# LEDProbe.net
KiCad netlist of a schematic drawn in EAGLE
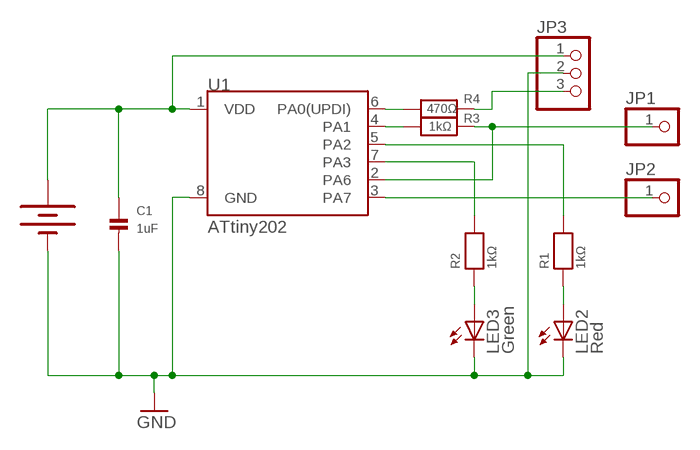
[diagram p0: schematic, sheet 1]

(export (version "E")
  (design (tool "Eeschema 10.0.6"))
  (components
    (comp (ref "BAT2")
      (value "20mm coincell")
      (footprint "eagle-import:BATTCON_20MM_4LEGS")
      (libsource (lib "eagle-import") (part "BATTERY20MM_4LEGS"))
    )
    (comp (ref "C1")
      (value "1uF")
      (footprint "eagle-import:_0805MP")
      (libsource (lib "eagle-import") (part "CAP_CERAMIC_0805MP"))
    )
    (comp (ref "JP1")
      (value "PINHD-1X1CB")
      (footprint "eagle-import:1X01-CLEANBIG")
      (libsource (lib "eagle-import") (part "PINHD-1X1CB"))
    )
    (comp (ref "JP2")
      (value "PINHD-1X1CB")
      (footprint "eagle-import:1X01-CLEANBIG")
      (libsource (lib "eagle-import") (part "PINHD-1X1CB"))
    )
    (comp (ref "JP3")
      (value "PINHD-1X3CB")
      (footprint "eagle-import:1X03-CLEANBIG")
      (libsource (lib "eagle-import") (part "PINHD-1X3CB"))
    )
    (comp (ref "LED2")
      (value "Red")
      (footprint "eagle-import:CHIPLED_0805")
      (libsource (lib "eagle-import") (part "LEDCHIPLED_0805"))
    )
    (comp (ref "LED3")
      (value "Green")
      (footprint "eagle-import:CHIPLED_0805")
      (libsource (lib "eagle-import") (part "LEDCHIPLED_0805"))
    )
    (comp (ref "R1")
      (value "1kΩ")
      (footprint "eagle-import:_0805MP")
      (libsource (lib "eagle-import") (part "RESISTOR_0805MP"))
    )
    (comp (ref "R2")
      (value "1kΩ")
      (footprint "eagle-import:_0805MP")
      (libsource (lib "eagle-import") (part "RESISTOR_0805MP"))
    )
    (comp (ref "R3")
      (value "1kΩ")
      (footprint "eagle-import:_0805MP")
      (libsource (lib "eagle-import") (part "RESISTOR_0805MP"))
    )
    (comp (ref "R4")
      (value "470Ω")
      (footprint "eagle-import:_0805MP")
      (libsource (lib "eagle-import") (part "RESISTOR_0805MP"))
    )
    (comp (ref "U1")
      (value "ATtiny202")
      (footprint "eagle-import:SO08-EIAJ")
      (libsource (lib "eagle-import") (part "ATTINY402ATTINY402-SMT"))
    )
  )
  (nets
    (net (code "1") (name "GND") (class "Default")
      (node (ref "BAT2") (pin "NEGATIVE") (pinfunction "-_NEGATIVE") (pintype "power_in"))
      (node (ref "C1") (pin "2") (pinfunction "P$2_2") (pintype "passive"))
      (node (ref "JP3") (pin "2") (pinfunction "2_2") (pintype "passive"))
      (node (ref "LED2") (pin "C") (pinfunction "C_C") (pintype "passive"))
      (node (ref "LED3") (pin "C") (pinfunction "C_C") (pintype "passive"))
      (node (ref "U1") (pin "8") (pinfunction "GND_8") (pintype "power_in"))
    )
    (net (code "2") (name "Net-(C1-P$1)") (class "Default")
      (node (ref "BAT2") (pin "POSITIVE@1") (pinfunction "+_POSITIVE@1") (pintype "power_in"))
      (node (ref "BAT2") (pin "POSITIVE@2") (pinfunction "+_POSITIVE@2") (pintype "power_in"))
      (node (ref "BAT2") (pin "POSITIVE@3") (pinfunction "+_POSITIVE@3") (pintype "power_in"))
      (node (ref "BAT2") (pin "POSITIVE@4") (pinfunction "+_POSITIVE@4") (pintype "power_in"))
      (node (ref "C1") (pin "1") (pinfunction "P$1_1") (pintype "passive"))
      (node (ref "JP3") (pin "1") (pinfunction "1_1") (pintype "passive"))
      (node (ref "U1") (pin "1") (pinfunction "VDD_1") (pintype "power_in"))
    )
    (net (code "3") (name "Net-(JP3-Pad3)") (class "Default")
      (node (ref "JP3") (pin "3") (pinfunction "3_3") (pintype "passive"))
      (node (ref "R4") (pin "1") (pinfunction "1_1") (pintype "passive"))
    )
    (net (code "4") (name "Net-(LED2-PadA)") (class "Default")
      (node (ref "LED2") (pin "A") (pinfunction "A_A") (pintype "passive"))
      (node (ref "R1") (pin "1") (pinfunction "1_1") (pintype "passive"))
    )
    (net (code "5") (name "Net-(LED3-PadA)") (class "Default")
      (node (ref "LED3") (pin "A") (pinfunction "A_A") (pintype "passive"))
      (node (ref "R2") (pin "1") (pinfunction "1_1") (pintype "passive"))
    )
    (net (code "6") (name "Net-(U1-PA0(UPDI))") (class "Default")
      (node (ref "R4") (pin "2") (pinfunction "2_2") (pintype "passive"))
      (node (ref "U1") (pin "6") (pinfunction "PA0(UPDI)_6") (pintype "bidirectional"))
    )
    (net (code "7") (name "Net-(U1-PA1)") (class "Default")
      (node (ref "R3") (pin "2") (pinfunction "2_2") (pintype "passive"))
      (node (ref "U1") (pin "4") (pinfunction "PA1_4") (pintype "bidirectional"))
    )
    (net (code "8") (name "Net-(U1-PA2)") (class "Default")
      (node (ref "R1") (pin "2") (pinfunction "2_2") (pintype "passive"))
      (node (ref "U1") (pin "5") (pinfunction "PA2_5") (pintype "bidirectional"))
    )
    (net (code "9") (name "Net-(U1-PA3)") (class "Default")
      (node (ref "R2") (pin "2") (pinfunction "2_2") (pintype "passive"))
      (node (ref "U1") (pin "7") (pinfunction "PA3_7") (pintype "bidirectional"))
    )
    (net (code "10") (name "Net-(U1-PA6)") (class "Default")
      (node (ref "JP1") (pin "1") (pinfunction "1_1") (pintype "passive"))
      (node (ref "R3") (pin "1") (pinfunction "1_1") (pintype "passive"))
      (node (ref "U1") (pin "2") (pinfunction "PA6_2") (pintype "bidirectional"))
    )
    (net (code "11") (name "Net-(U1-PA7)") (class "Default")
      (node (ref "JP2") (pin "1") (pinfunction "1_1") (pintype "passive"))
      (node (ref "U1") (pin "3") (pinfunction "PA7_3") (pintype "bidirectional"))
    )
  )
)
